# audiostick_v1.net
KiCad netlist of a schematic drawn in EAGLE
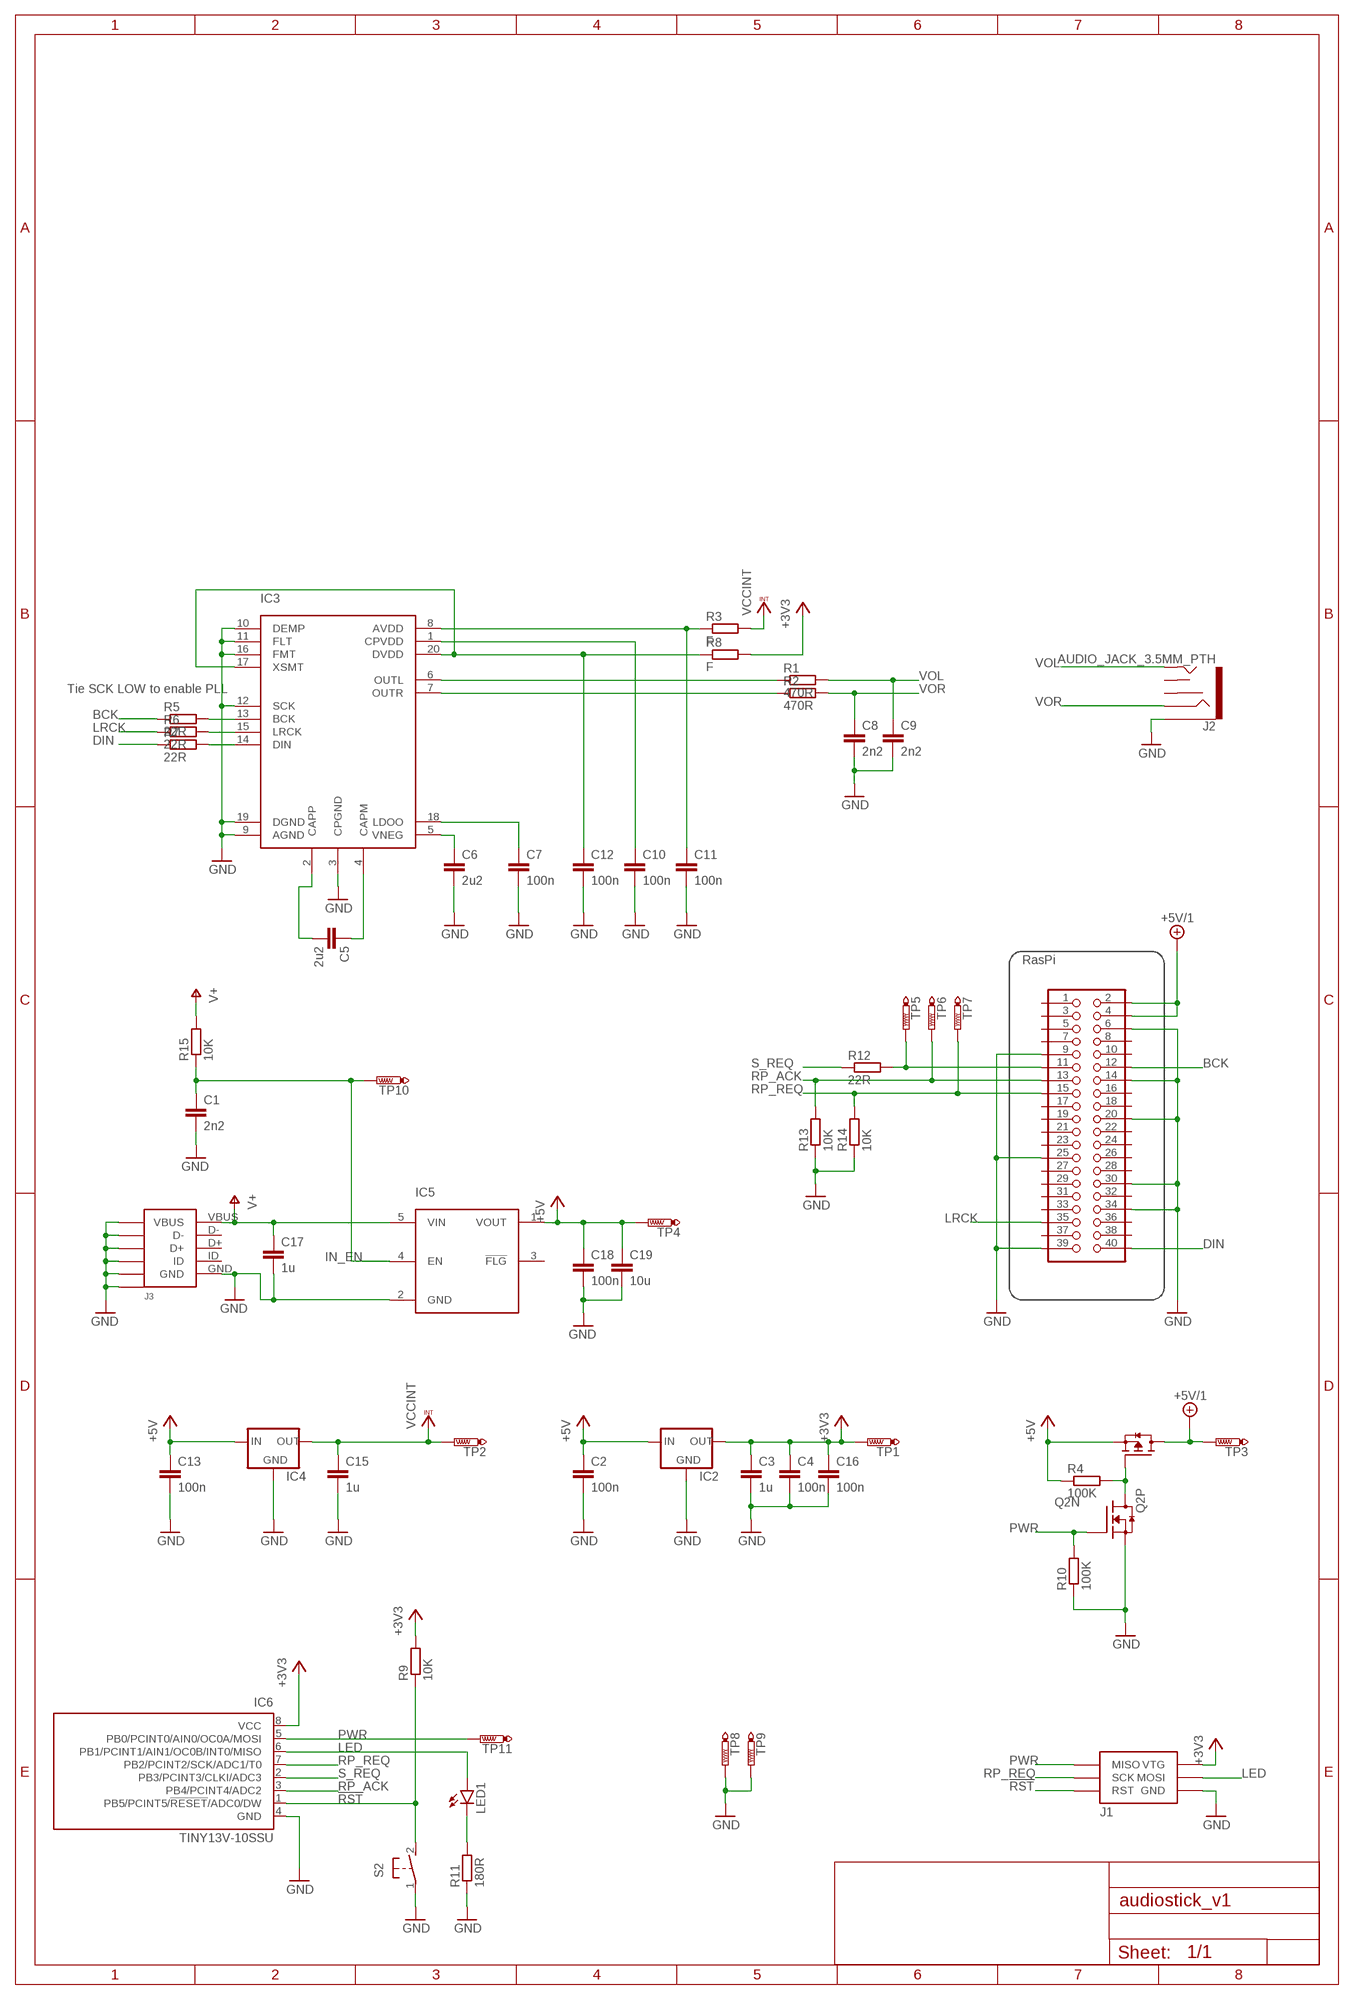
[diagram p0: schematic, sheet 1]

(export (version "E")
  (design (tool "Eeschema 10.0.6"))
  (components
    (comp (ref "C1")
      (value "2n2")
      (footprint "eagle-import:C0603")
      (libsource (lib "eagle-import") (part "C-EUC0603"))
    )
    (comp (ref "C2")
      (value "100n")
      (footprint "eagle-import:C0805")
      (libsource (lib "eagle-import") (part "C-EUC0805"))
    )
    (comp (ref "C3")
      (value "1u")
      (footprint "eagle-import:C0805")
      (libsource (lib "eagle-import") (part "C-EUC0805"))
    )
    (comp (ref "C4")
      (value "100n")
      (footprint "eagle-import:C0805")
      (libsource (lib "eagle-import") (part "C-EUC0805"))
    )
    (comp (ref "C5")
      (value "2u2")
      (footprint "eagle-import:C0603")
      (libsource (lib "eagle-import") (part "C-EUC0603"))
    )
    (comp (ref "C6")
      (value "2u2")
      (footprint "eagle-import:C0603")
      (libsource (lib "eagle-import") (part "C-EUC0603"))
    )
    (comp (ref "C7")
      (value "100n")
      (footprint "eagle-import:C0603")
      (libsource (lib "eagle-import") (part "C-EUC0603"))
    )
    (comp (ref "C8")
      (value "2n2")
      (footprint "eagle-import:C0603")
      (libsource (lib "eagle-import") (part "C-EUC0603"))
    )
    (comp (ref "C9")
      (value "2n2")
      (footprint "eagle-import:C0603")
      (libsource (lib "eagle-import") (part "C-EUC0603"))
    )
    (comp (ref "C10")
      (value "100n")
      (footprint "eagle-import:C0603")
      (libsource (lib "eagle-import") (part "C-EUC0603"))
    )
    (comp (ref "C11")
      (value "100n")
      (footprint "eagle-import:C0603")
      (libsource (lib "eagle-import") (part "C-EUC0603"))
    )
    (comp (ref "C12")
      (value "100n")
      (footprint "eagle-import:C0603")
      (libsource (lib "eagle-import") (part "C-EUC0603"))
    )
    (comp (ref "C13")
      (value "100n")
      (footprint "eagle-import:C0805")
      (libsource (lib "eagle-import") (part "C-EUC0805"))
    )
    (comp (ref "C15")
      (value "1u")
      (footprint "eagle-import:C0805")
      (libsource (lib "eagle-import") (part "C-EUC0805"))
    )
    (comp (ref "C16")
      (value "100n")
      (footprint "eagle-import:C0805")
      (libsource (lib "eagle-import") (part "C-EUC0805"))
    )
    (comp (ref "C17")
      (value "1u")
      (footprint "eagle-import:C0805")
      (libsource (lib "eagle-import") (part "C-EUC0805"))
    )
    (comp (ref "C18")
      (value "100n")
      (footprint "eagle-import:C0603")
      (libsource (lib "eagle-import") (part "C-EUC0603"))
    )
    (comp (ref "C19")
      (value "10u")
      (footprint "eagle-import:C0805")
      (libsource (lib "eagle-import") (part "C-EUC0805"))
    )
    (comp (ref "IC2")
      (value "MCP1700TT")
      (footprint "eagle-import:SOT-23")
      (libsource (lib "eagle-import") (part "MCP1700TT"))
    )
    (comp (ref "IC3")
      (value "PCM5102ASW")
      (footprint "eagle-import:TSSOP20")
      (libsource (lib "eagle-import") (part "PCM5102ASW"))
    )
    (comp (ref "IC4")
      (value "MCP1700TT")
      (footprint "eagle-import:SOT-23")
      (libsource (lib "eagle-import") (part "MCP1700TT"))
    )
    (comp (ref "IC5")
      (value "AP22804W5")
      (footprint "eagle-import:GHI_SOT23-5")
      (libsource (lib "eagle-import") (part "AP22804W5"))
    )
    (comp (ref "IC6")
      (value "TINY13V-10SSU")
      (footprint "eagle-import:8S1")
      (fields (field (name "MPN") "ATTINY13V-10SSU"))
      (libsource (lib "eagle-import") (part "TINY13SSUV-10"))
    )
    (comp (ref "J1")
      (value "AVRISP6TH127")
      (footprint "eagle-import:2X3-50MIL")
      (libsource (lib "eagle-import") (part "AVRISP6TH127"))
    )
    (comp (ref "J2")
      (value "AUDIO_JACK_3.5MM_PTH")
      (footprint "eagle-import:AUDIO-JACK")
      (libsource (lib "eagle-import") (part "AUDIO_JACK_3.5MM_PTH"))
    )
    (comp (ref "J3")
      (value "USB-B")
      (footprint "eagle-import:1050170001")
      (libsource (lib "eagle-import") (part "USB-B"))
    )
    (comp (ref "LED1")
      (value "LED3MM")
      (footprint "eagle-import:LED3MM")
      (libsource (lib "eagle-import") (part "LED3MM"))
    )
    (comp (ref "Q2")
      (value "BSL215")
      (footprint "eagle-import:6TSOP")
      (libsource (lib "eagle-import") (part "BSL215"))
    )
    (comp (ref "R1")
      (value "470R")
      (footprint "eagle-import:R0603")
      (libsource (lib "eagle-import") (part "R-EU_R0603"))
    )
    (comp (ref "R2")
      (value "470R")
      (footprint "eagle-import:R0603")
      (libsource (lib "eagle-import") (part "R-EU_R0603"))
    )
    (comp (ref "R3")
      (value "F")
      (footprint "eagle-import:R0603")
      (libsource (lib "eagle-import") (part "R-EU_R0603"))
    )
    (comp (ref "R4")
      (value "100K")
      (footprint "eagle-import:R0805")
      (libsource (lib "eagle-import") (part "R-EU_R0805"))
    )
    (comp (ref "R5")
      (value "22R")
      (footprint "eagle-import:R0603")
      (libsource (lib "eagle-import") (part "R-EU_R0603"))
    )
    (comp (ref "R6")
      (value "22R")
      (footprint "eagle-import:R0603")
      (libsource (lib "eagle-import") (part "R-EU_R0603"))
    )
    (comp (ref "R7")
      (value "22R")
      (footprint "eagle-import:R0603")
      (libsource (lib "eagle-import") (part "R-EU_R0603"))
    )
    (comp (ref "R8")
      (value "F")
      (footprint "eagle-import:R0603")
      (libsource (lib "eagle-import") (part "R-EU_R0603"))
    )
    (comp (ref "R9")
      (value "10K")
      (footprint "eagle-import:R0603")
      (libsource (lib "eagle-import") (part "R-EU_R0603"))
    )
    (comp (ref "R10")
      (value "100K")
      (footprint "eagle-import:R0805")
      (libsource (lib "eagle-import") (part "R-EU_R0805"))
    )
    (comp (ref "R11")
      (value "180R")
      (footprint "eagle-import:R0805")
      (libsource (lib "eagle-import") (part "R-EU_R0805"))
    )
    (comp (ref "R12")
      (value "22R")
      (footprint "eagle-import:R0603")
      (libsource (lib "eagle-import") (part "R-EU_R0603"))
    )
    (comp (ref "R13")
      (value "10K")
      (footprint "eagle-import:R0603")
      (libsource (lib "eagle-import") (part "R-EU_R0603"))
    )
    (comp (ref "R14")
      (value "10K")
      (footprint "eagle-import:R0603")
      (libsource (lib "eagle-import") (part "R-EU_R0603"))
    )
    (comp (ref "R15")
      (value "10K")
      (footprint "eagle-import:R0603")
      (libsource (lib "eagle-import") (part "R-EU_R0603"))
    )
    (comp (ref "S2")
      (value "31-XX")
      (footprint "eagle-import:B3F-31XX")
      (fields (field (name "MPN") "B3F-3100"))
      (libsource (lib "eagle-import") (part "31-XX"))
    )
    (comp (ref "TP1")
      (value "PTR1PAD1-13")
      (footprint "eagle-import:P1-13")
      (libsource (lib "eagle-import") (part "PTR1PAD1-13"))
    )
    (comp (ref "TP2")
      (value "PTR1PAD1-13")
      (footprint "eagle-import:P1-13")
      (libsource (lib "eagle-import") (part "PTR1PAD1-13"))
    )
    (comp (ref "TP3")
      (value "PTR1PAD1-13")
      (footprint "eagle-import:P1-13")
      (libsource (lib "eagle-import") (part "PTR1PAD1-13"))
    )
    (comp (ref "TP4")
      (value "PTR1PAD1-13")
      (footprint "eagle-import:P1-13")
      (libsource (lib "eagle-import") (part "PTR1PAD1-13"))
    )
    (comp (ref "TP5")
      (value "PTR1PAD1-13")
      (footprint "eagle-import:P1-13")
      (libsource (lib "eagle-import") (part "PTR1PAD1-13"))
    )
    (comp (ref "TP6")
      (value "PTR1PAD1-13")
      (footprint "eagle-import:P1-13")
      (libsource (lib "eagle-import") (part "PTR1PAD1-13"))
    )
    (comp (ref "TP7")
      (value "PTR1PAD1-13")
      (footprint "eagle-import:P1-13")
      (libsource (lib "eagle-import") (part "PTR1PAD1-13"))
    )
    (comp (ref "TP8")
      (value "PTR1PAD1-13")
      (footprint "eagle-import:P1-13")
      (libsource (lib "eagle-import") (part "PTR1PAD1-13"))
    )
    (comp (ref "TP9")
      (value "PTR1PAD1-13")
      (footprint "eagle-import:P1-13")
      (libsource (lib "eagle-import") (part "PTR1PAD1-13"))
    )
    (comp (ref "TP10")
      (value "PTR1PAD1-13")
      (footprint "eagle-import:P1-13")
      (libsource (lib "eagle-import") (part "PTR1PAD1-13"))
    )
    (comp (ref "TP11")
      (value "PTR1PAD1-13")
      (footprint "eagle-import:P1-13")
      (libsource (lib "eagle-import") (part "PTR1PAD1-13"))
    )
    (comp (ref "U$1")
      (value "RASPIZERO")
      (footprint "eagle-import:RASPIZERO")
      (libsource (lib "eagle-import") (part "RASPIZERO"))
    )
  )
  (nets
    (net (code "1") (name "+3V3") (class "Default")
      (node (ref "C16") (pin "1") (pinfunction "1_1") (pintype "passive"))
      (node (ref "C3") (pin "1") (pinfunction "1_1") (pintype "passive"))
      (node (ref "C4") (pin "1") (pinfunction "1_1") (pintype "passive"))
      (node (ref "IC2") (pin "2") (pinfunction "OUT_2") (pintype "passive"))
      (node (ref "IC6") (pin "8") (pinfunction "VCC_8") (pintype "power_in"))
      (node (ref "J1") (pin "2") (pinfunction "VTG_2") (pintype "bidirectional"))
      (node (ref "R8") (pin "2") (pinfunction "2_2") (pintype "passive"))
      (node (ref "R9") (pin "2") (pinfunction "2_2") (pintype "passive"))
      (node (ref "TP1") (pin "TP") (pinfunction "TP_TP") (pintype "input"))
    )
    (net (code "2") (name "+5V") (class "Default")
      (node (ref "C13") (pin "1") (pinfunction "1_1") (pintype "passive"))
      (node (ref "C18") (pin "1") (pinfunction "1_1") (pintype "passive"))
      (node (ref "C19") (pin "1") (pinfunction "1_1") (pintype "passive"))
      (node (ref "C2") (pin "1") (pinfunction "1_1") (pintype "passive"))
      (node (ref "IC2") (pin "3") (pinfunction "IN_3") (pintype "input"))
      (node (ref "IC4") (pin "3") (pinfunction "IN_3") (pintype "input"))
      (node (ref "IC5") (pin "1") (pinfunction "VOUT_1") (pintype "power_in"))
      (node (ref "Q2") (pin "2") (pinfunction "S_2") (pintype "passive"))
      (node (ref "R4") (pin "1") (pinfunction "1_1") (pintype "passive"))
      (node (ref "TP4") (pin "TP") (pinfunction "TP_TP") (pintype "input"))
    )
    (net (code "3") (name "+5V{slash}1") (class "Default")
      (node (ref "Q2") (pin "4") (pinfunction "D_4") (pintype "passive"))
      (node (ref "TP3") (pin "TP") (pinfunction "TP_TP") (pintype "input"))
      (node (ref "U$1") (pin "2") (pinfunction "5V_2") (pintype "passive"))
      (node (ref "U$1") (pin "4") (pinfunction "5V_4") (pintype "passive"))
    )
    (net (code "4") (name "/BCK") (class "Default")
      (node (ref "R5") (pin "1") (pinfunction "1_1") (pintype "passive"))
      (node (ref "U$1") (pin "12") (pinfunction "18_12") (pintype "passive"))
    )
    (net (code "5") (name "/DIN") (class "Default")
      (node (ref "R7") (pin "1") (pinfunction "1_1") (pintype "passive"))
      (node (ref "U$1") (pin "40") (pinfunction "21_40") (pintype "passive"))
    )
    (net (code "6") (name "/IN_EN") (class "Default")
      (node (ref "C1") (pin "1") (pinfunction "1_1") (pintype "passive"))
      (node (ref "IC5") (pin "4") (pinfunction "EN_4") (pintype "input"))
      (node (ref "R15") (pin "1") (pinfunction "1_1") (pintype "passive"))
      (node (ref "TP10") (pin "TP") (pinfunction "TP_TP") (pintype "input"))
    )
    (net (code "7") (name "/LED") (class "Default")
      (node (ref "IC6") (pin "6") (pinfunction "PB1/PCINT1/AIN1/OC0B/INT0/MISO_6") (pintype "bidirectional"))
      (node (ref "J1") (pin "4") (pinfunction "MOSI_4") (pintype "bidirectional"))
      (node (ref "LED1") (pin "A") (pinfunction "A_A") (pintype "passive"))
    )
    (net (code "8") (name "/LRCK") (class "Default")
      (node (ref "R6") (pin "1") (pinfunction "1_1") (pintype "passive"))
      (node (ref "U$1") (pin "35") (pinfunction "19_35") (pintype "passive"))
    )
    (net (code "9") (name "/PWR") (class "Default")
      (node (ref "IC6") (pin "5") (pinfunction "PB0/PCINT0/AIN0/OC0A/MOSI_5") (pintype "bidirectional"))
      (node (ref "J1") (pin "1") (pinfunction "MISO_1") (pintype "bidirectional"))
      (node (ref "Q2") (pin "1") (pinfunction "G_1") (pintype "passive"))
      (node (ref "R10") (pin "2") (pinfunction "2_2") (pintype "passive"))
      (node (ref "TP11") (pin "TP") (pinfunction "TP_TP") (pintype "input"))
    )
    (net (code "10") (name "/RP_ACK") (class "Default")
      (node (ref "IC6") (pin "3") (pinfunction "PB4/PCINT4/ADC2_3") (pintype "bidirectional"))
      (node (ref "R13") (pin "2") (pinfunction "2_2") (pintype "passive"))
      (node (ref "TP6") (pin "TP") (pinfunction "TP_TP") (pintype "input"))
      (node (ref "U$1") (pin "13") (pinfunction "27_13") (pintype "passive"))
    )
    (net (code "11") (name "/RP_REQ") (class "Default")
      (node (ref "IC6") (pin "7") (pinfunction "PB2/PCINT2/SCK/ADC1/T0_7") (pintype "bidirectional"))
      (node (ref "J1") (pin "3") (pinfunction "SCK_3") (pintype "bidirectional"))
      (node (ref "R14") (pin "2") (pinfunction "2_2") (pintype "passive"))
      (node (ref "TP7") (pin "TP") (pinfunction "TP_TP") (pintype "input"))
      (node (ref "U$1") (pin "15") (pinfunction "22_15") (pintype "passive"))
    )
    (net (code "12") (name "/S_REQ") (class "Default")
      (node (ref "IC6") (pin "2") (pinfunction "PB3/PCINT3/CLKI/ADC3_2") (pintype "bidirectional"))
      (node (ref "R12") (pin "1") (pinfunction "1_1") (pintype "passive"))
    )
    (net (code "13") (name "/VOL") (class "Default")
      (node (ref "C9") (pin "1") (pinfunction "1_1") (pintype "passive"))
      (node (ref "J2") (pin "TIP") (pinfunction "TIP_TIP") (pintype "bidirectional"))
      (node (ref "R1") (pin "2") (pinfunction "2_2") (pintype "passive"))
    )
    (net (code "14") (name "/VOR") (class "Default")
      (node (ref "C8") (pin "1") (pinfunction "1_1") (pintype "passive"))
      (node (ref "J2") (pin "RING") (pinfunction "RING_RING") (pintype "bidirectional"))
      (node (ref "R2") (pin "2") (pinfunction "2_2") (pintype "passive"))
    )
    (net (code "15") (name "/~{RST}") (class "Default")
      (node (ref "IC6") (pin "1") (pinfunction "PB5/PCINT5/~{RESET}/ADC0/DW_1") (pintype "bidirectional"))
      (node (ref "J1") (pin "5") (pinfunction "RST_5") (pintype "bidirectional"))
      (node (ref "R9") (pin "1") (pinfunction "1_1") (pintype "passive"))
      (node (ref "S2") (pin "2") (pinfunction "S_2") (pintype "passive"))
    )
    (net (code "16") (name "GND") (class "Default")
      (node (ref "C1") (pin "2") (pinfunction "2_2") (pintype "passive"))
      (node (ref "C10") (pin "2") (pinfunction "2_2") (pintype "passive"))
      (node (ref "C11") (pin "2") (pinfunction "2_2") (pintype "passive"))
      (node (ref "C12") (pin "2") (pinfunction "2_2") (pintype "passive"))
      (node (ref "C13") (pin "2") (pinfunction "2_2") (pintype "passive"))
      (node (ref "C15") (pin "2") (pinfunction "2_2") (pintype "passive"))
      (node (ref "C16") (pin "2") (pinfunction "2_2") (pintype "passive"))
      (node (ref "C17") (pin "2") (pinfunction "2_2") (pintype "passive"))
      (node (ref "C18") (pin "2") (pinfunction "2_2") (pintype "passive"))
      (node (ref "C19") (pin "2") (pinfunction "2_2") (pintype "passive"))
      (node (ref "C2") (pin "2") (pinfunction "2_2") (pintype "passive"))
      (node (ref "C3") (pin "2") (pinfunction "2_2") (pintype "passive"))
      (node (ref "C4") (pin "2") (pinfunction "2_2") (pintype "passive"))
      (node (ref "C6") (pin "2") (pinfunction "2_2") (pintype "passive"))
      (node (ref "C7") (pin "2") (pinfunction "2_2") (pintype "passive"))
      (node (ref "C8") (pin "2") (pinfunction "2_2") (pintype "passive"))
      (node (ref "C9") (pin "2") (pinfunction "2_2") (pintype "passive"))
      (node (ref "IC2") (pin "1") (pinfunction "GND_1") (pintype "input"))
      (node (ref "IC3") (pin "10") (pinfunction "DEMP_10") (pintype "input"))
      (node (ref "IC3") (pin "11") (pinfunction "FLT_11") (pintype "input"))
      (node (ref "IC3") (pin "12") (pinfunction "SCK_12") (pintype "input"))
      (node (ref "IC3") (pin "16") (pinfunction "FMT_16") (pintype "input"))
      (node (ref "IC3") (pin "19") (pinfunction "DGND_19") (pintype "power_in"))
      (node (ref "IC3") (pin "3") (pinfunction "CPGND_3") (pintype "output"))
      (node (ref "IC3") (pin "9") (pinfunction "AGND_9") (pintype "power_in"))
      (node (ref "IC4") (pin "1") (pinfunction "GND_1") (pintype "input"))
      (node (ref "IC5") (pin "2") (pinfunction "GND_2") (pintype "power_in"))
      (node (ref "IC6") (pin "4") (pinfunction "GND_4") (pintype "power_in"))
      (node (ref "J1") (pin "6") (pinfunction "GND_6") (pintype "bidirectional"))
      (node (ref "J2") (pin "SLEEVE") (pinfunction "SLEEVE_SLEEVE") (pintype "bidirectional"))
      (node (ref "J3") (pin "GND") (pinfunction "GND_GND") (pintype "power_in"))
      (node (ref "J3") (pin "P$1") (pinfunction "SH1*4_P$1") (pintype "power_in"))
      (node (ref "J3") (pin "P$10") (pinfunction "SH1*5_P$10") (pintype "power_in"))
      (node (ref "J3") (pin "P$11") (pinfunction "SH1*6_P$11") (pintype "power_in"))
      (node (ref "J3") (pin "P$2") (pinfunction "SH1*1_P$2") (pintype "power_in"))
      (node (ref "J3") (pin "P$3") (pinfunction "SH1*2_P$3") (pintype "power_in"))
      (node (ref "J3") (pin "P$4") (pinfunction "SH1*3_P$4") (pintype "power_in"))
      (node (ref "Q2") (pin "5") (pinfunction "S_5") (pintype "passive"))
      (node (ref "R10") (pin "1") (pinfunction "1_1") (pintype "passive"))
      (node (ref "R11") (pin "1") (pinfunction "1_1") (pintype "passive"))
      (node (ref "R13") (pin "1") (pinfunction "1_1") (pintype "passive"))
      (node (ref "R14") (pin "1") (pinfunction "1_1") (pintype "passive"))
      (node (ref "S2") (pin "1") (pinfunction "P_1") (pintype "passive"))
      (node (ref "TP8") (pin "TP") (pinfunction "TP_TP") (pintype "input"))
      (node (ref "TP9") (pin "TP") (pinfunction "TP_TP") (pintype "input"))
      (node (ref "U$1") (pin "14") (pinfunction "GND_14") (pintype "passive"))
      (node (ref "U$1") (pin "20") (pinfunction "GND_20") (pintype "passive"))
      (node (ref "U$1") (pin "25") (pinfunction "GND_25") (pintype "passive"))
      (node (ref "U$1") (pin "30") (pinfunction "GND_30") (pintype "passive"))
      (node (ref "U$1") (pin "34") (pinfunction "GND_34") (pintype "passive"))
      (node (ref "U$1") (pin "39") (pinfunction "GND_39") (pintype "passive"))
      (node (ref "U$1") (pin "6") (pinfunction "GND_6") (pintype "passive"))
      (node (ref "U$1") (pin "9") (pinfunction "GND_9") (pintype "passive"))
    )
    (net (code "17") (name "Net-(IC3-AVDD)") (class "Default")
      (node (ref "C11") (pin "1") (pinfunction "1_1") (pintype "passive"))
      (node (ref "IC3") (pin "8") (pinfunction "AVDD_8") (pintype "power_in"))
      (node (ref "R3") (pin "1") (pinfunction "1_1") (pintype "passive"))
    )
    (net (code "18") (name "Net-(IC3-BCK)") (class "Default")
      (node (ref "IC3") (pin "13") (pinfunction "BCK_13") (pintype "input"))
      (node (ref "R5") (pin "2") (pinfunction "2_2") (pintype "passive"))
    )
    (net (code "19") (name "Net-(IC3-CAPM)") (class "Default")
      (node (ref "C5") (pin "1") (pinfunction "1_1") (pintype "passive"))
      (node (ref "IC3") (pin "4") (pinfunction "CAPM_4") (pintype "output"))
    )
    (net (code "20") (name "Net-(IC3-CAPP)") (class "Default")
      (node (ref "C5") (pin "2") (pinfunction "2_2") (pintype "passive"))
      (node (ref "IC3") (pin "2") (pinfunction "CAPP_2") (pintype "output"))
    )
    (net (code "21") (name "Net-(IC3-CPVDD)") (class "Default")
      (node (ref "C10") (pin "1") (pinfunction "1_1") (pintype "passive"))
      (node (ref "IC3") (pin "1") (pinfunction "CPVDD_1") (pintype "power_in"))
    )
    (net (code "22") (name "Net-(IC3-DIN)") (class "Default")
      (node (ref "IC3") (pin "14") (pinfunction "DIN_14") (pintype "input"))
      (node (ref "R7") (pin "2") (pinfunction "2_2") (pintype "passive"))
    )
    (net (code "23") (name "Net-(IC3-DVDD)") (class "Default")
      (node (ref "C12") (pin "1") (pinfunction "1_1") (pintype "passive"))
      (node (ref "IC3") (pin "17") (pinfunction "XSMT_17") (pintype "input"))
      (node (ref "IC3") (pin "20") (pinfunction "DVDD_20") (pintype "power_in"))
      (node (ref "R8") (pin "1") (pinfunction "1_1") (pintype "passive"))
    )
    (net (code "24") (name "Net-(IC3-LDOO)") (class "Default")
      (node (ref "C7") (pin "1") (pinfunction "1_1") (pintype "passive"))
      (node (ref "IC3") (pin "18") (pinfunction "LDOO_18") (pintype "power_in"))
    )
    (net (code "25") (name "Net-(IC3-LRCK)") (class "Default")
      (node (ref "IC3") (pin "15") (pinfunction "LRCK_15") (pintype "input"))
      (node (ref "R6") (pin "2") (pinfunction "2_2") (pintype "passive"))
    )
    (net (code "26") (name "Net-(IC3-OUTL)") (class "Default")
      (node (ref "IC3") (pin "6") (pinfunction "OUTL_6") (pintype "output"))
      (node (ref "R1") (pin "1") (pinfunction "1_1") (pintype "passive"))
    )
    (net (code "27") (name "Net-(IC3-OUTR)") (class "Default")
      (node (ref "IC3") (pin "7") (pinfunction "OUTR_7") (pintype "output"))
      (node (ref "R2") (pin "1") (pinfunction "1_1") (pintype "passive"))
    )
    (net (code "28") (name "Net-(IC3-VNEG)") (class "Default")
      (node (ref "C6") (pin "1") (pinfunction "1_1") (pintype "passive"))
      (node (ref "IC3") (pin "5") (pinfunction "VNEG_5") (pintype "power_in"))
    )
    (net (code "29") (name "Net-(LED1-C)") (class "Default")
      (node (ref "LED1") (pin "K") (pinfunction "C_K") (pintype "passive"))
      (node (ref "R11") (pin "2") (pinfunction "2_2") (pintype "passive"))
    )
    (net (code "30") (name "Net-(Q2A-D)") (class "Default")
      (node (ref "Q2") (pin "3") (pinfunction "G_3") (pintype "passive"))
      (node (ref "Q2") (pin "6") (pinfunction "D_6") (pintype "passive"))
      (node (ref "R4") (pin "2") (pinfunction "2_2") (pintype "passive"))
    )
    (net (code "31") (name "Net-(U$1-17)") (class "Default")
      (node (ref "R12") (pin "2") (pinfunction "2_2") (pintype "passive"))
      (node (ref "TP5") (pin "TP") (pinfunction "TP_TP") (pintype "input"))
      (node (ref "U$1") (pin "11") (pinfunction "17_11") (pintype "passive"))
    )
    (net (code "32") (name "V+") (class "Default")
      (node (ref "C17") (pin "1") (pinfunction "1_1") (pintype "passive"))
      (node (ref "IC5") (pin "5") (pinfunction "VIN_5") (pintype "power_in"))
      (node (ref "J3") (pin "VBUS") (pinfunction "VBUS_VBUS") (pintype "power_in"))
      (node (ref "R15") (pin "2") (pinfunction "2_2") (pintype "passive"))
    )
    (net (code "33") (name "VCCINT") (class "Default")
      (node (ref "C15") (pin "1") (pinfunction "1_1") (pintype "passive"))
      (node (ref "IC4") (pin "2") (pinfunction "OUT_2") (pintype "passive"))
      (node (ref "R3") (pin "2") (pinfunction "2_2") (pintype "passive"))
      (node (ref "TP2") (pin "TP") (pinfunction "TP_TP") (pintype "input"))
    )
    (net (code "34") (name "unconnected-(IC5-~{FLG}-Pad3)") (class "Default")
      (node (ref "IC5") (pin "3") (pinfunction "~{FLG}_3") (pintype "open_collector"))
    )
    (net (code "35") (name "unconnected-(J2-PadRSH)") (class "Default")
      (node (ref "J2") (pin "RSH") (pinfunction "RSH_RSH") (pintype "bidirectional"))
    )
    (net (code "36") (name "unconnected-(J2-PadTSH)") (class "Default")
      (node (ref "J2") (pin "TSH") (pinfunction "TSH_TSH") (pintype "bidirectional"))
    )
    (net (code "37") (name "unconnected-(J3-PadD+)") (class "Default")
      (node (ref "J3") (pin "D+") (pinfunction "D+_D+") (pintype "bidirectional"))
    )
    (net (code "38") (name "unconnected-(J3-PadD-)") (class "Default")
      (node (ref "J3") (pin "D-") (pinfunction "D-_D-") (pintype "bidirectional"))
    )
    (net (code "39") (name "unconnected-(J3-PadID)") (class "Default")
      (node (ref "J3") (pin "ID") (pinfunction "ID_ID") (pintype "bidirectional"))
    )
    (net (code "40") (name "unconnected-(U$1-0-Pad27)") (class "Default")
      (node (ref "U$1") (pin "27") (pinfunction "0_27") (pintype "passive"))
    )
    (net (code "41") (name "unconnected-(U$1-1-Pad28)") (class "Default")
      (node (ref "U$1") (pin "28") (pinfunction "1_28") (pintype "passive"))
    )
    (net (code "42") (name "unconnected-(U$1-2-Pad3)") (class "Default")
      (node (ref "U$1") (pin "3") (pinfunction "2_3") (pintype "passive"))
    )
    (net (code "43") (name "unconnected-(U$1-3-Pad5)") (class "Default")
      (node (ref "U$1") (pin "5") (pinfunction "3_5") (pintype "passive"))
    )
    (net (code "44") (name "unconnected-(U$1-3V3-Pad1)") (class "Default")
      (node (ref "U$1") (pin "1") (pinfunction "3V3_1") (pintype "passive"))
    )
    (net (code "45") (name "unconnected-(U$1-3V3-Pad17)") (class "Default")
      (node (ref "U$1") (pin "17") (pinfunction "3V3_17") (pintype "passive"))
    )
    (net (code "46") (name "unconnected-(U$1-4-Pad7)") (class "Default")
      (node (ref "U$1") (pin "7") (pinfunction "4_7") (pintype "passive"))
    )
    (net (code "47") (name "unconnected-(U$1-5-Pad29)") (class "Default")
      (node (ref "U$1") (pin "29") (pinfunction "5_29") (pintype "passive"))
    )
    (net (code "48") (name "unconnected-(U$1-6-Pad31)") (class "Default")
      (node (ref "U$1") (pin "31") (pinfunction "6_31") (pintype "passive"))
    )
    (net (code "49") (name "unconnected-(U$1-7-Pad26)") (class "Default")
      (node (ref "U$1") (pin "26") (pinfunction "7_26") (pintype "passive"))
    )
    (net (code "50") (name "unconnected-(U$1-8-Pad24)") (class "Default")
      (node (ref "U$1") (pin "24") (pinfunction "8_24") (pintype "passive"))
    )
    (net (code "51") (name "unconnected-(U$1-9-Pad21)") (class "Default")
      (node (ref "U$1") (pin "21") (pinfunction "9_21") (pintype "passive"))
    )
    (net (code "52") (name "unconnected-(U$1-10-Pad19)") (class "Default")
      (node (ref "U$1") (pin "19") (pinfunction "10_19") (pintype "passive"))
    )
    (net (code "53") (name "unconnected-(U$1-11-Pad23)") (class "Default")
      (node (ref "U$1") (pin "23") (pinfunction "11_23") (pintype "passive"))
    )
    (net (code "54") (name "unconnected-(U$1-12-Pad32)") (class "Default")
      (node (ref "U$1") (pin "32") (pinfunction "12_32") (pintype "passive"))
    )
    (net (code "55") (name "unconnected-(U$1-13-Pad33)") (class "Default")
      (node (ref "U$1") (pin "33") (pinfunction "13_33") (pintype "passive"))
    )
    (net (code "56") (name "unconnected-(U$1-14-Pad8)") (class "Default")
      (node (ref "U$1") (pin "8") (pinfunction "14_8") (pintype "passive"))
    )
    (net (code "57") (name "unconnected-(U$1-15-Pad10)") (class "Default")
      (node (ref "U$1") (pin "10") (pinfunction "15_10") (pintype "passive"))
    )
    (net (code "58") (name "unconnected-(U$1-16-Pad36)") (class "Default")
      (node (ref "U$1") (pin "36") (pinfunction "16_36") (pintype "passive"))
    )
    (net (code "59") (name "unconnected-(U$1-20-Pad38)") (class "Default")
      (node (ref "U$1") (pin "38") (pinfunction "20_38") (pintype "passive"))
    )
    (net (code "60") (name "unconnected-(U$1-23-Pad16)") (class "Default")
      (node (ref "U$1") (pin "16") (pinfunction "23_16") (pintype "passive"))
    )
    (net (code "61") (name "unconnected-(U$1-24-Pad18)") (class "Default")
      (node (ref "U$1") (pin "18") (pinfunction "24_18") (pintype "passive"))
    )
    (net (code "62") (name "unconnected-(U$1-25-Pad22)") (class "Default")
      (node (ref "U$1") (pin "22") (pinfunction "25_22") (pintype "passive"))
    )
    (net (code "63") (name "unconnected-(U$1-26-Pad37)") (class "Default")
      (node (ref "U$1") (pin "37") (pinfunction "26_37") (pintype "passive"))
    )
  )
)
